# SerialGLCD.net
KiCad netlist of a schematic drawn in EAGLE
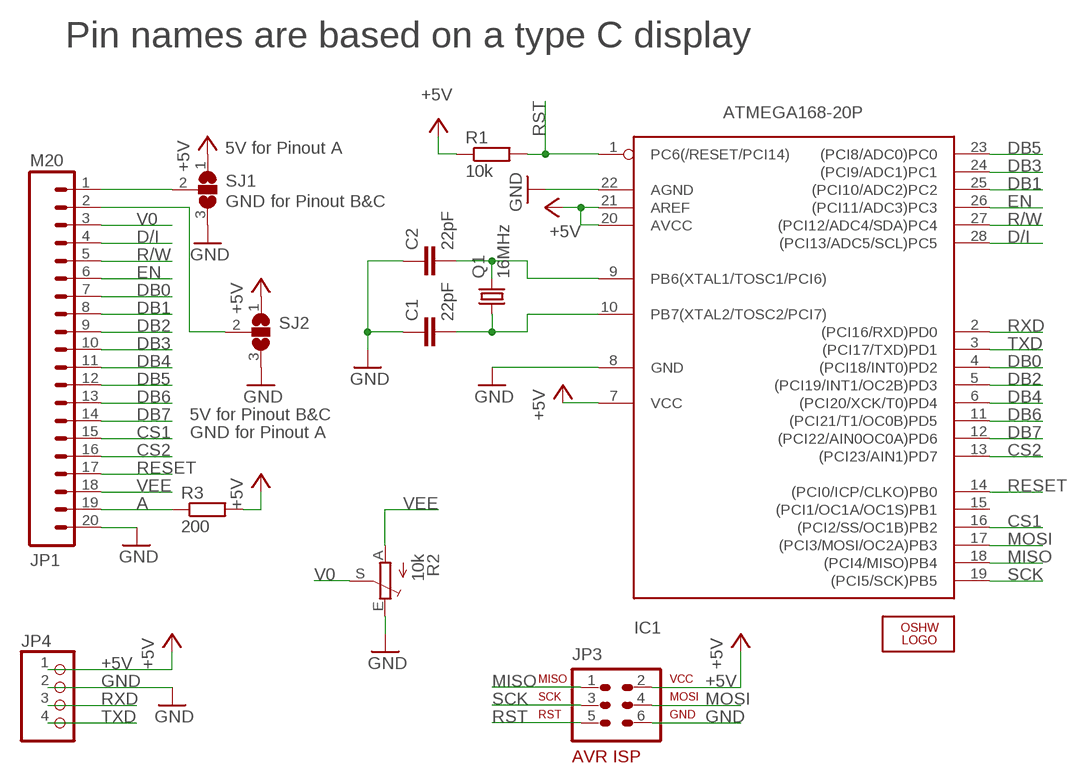
[diagram p0: schematic, sheet 1]

(export (version "E")
  (design (tool "Eeschema 10.0.6"))
  (components
    (comp (ref "C1")
      (value "22pF")
      (footprint "eagle-import:C025-024X044")
      (libsource (lib "eagle-import") (part "C-EU025-024X044"))
    )
    (comp (ref "C2")
      (value "22pF")
      (footprint "eagle-import:C025-024X044")
      (libsource (lib "eagle-import") (part "C-EU025-024X044"))
    )
    (comp (ref "IC1")
      (value "ATMEGA168-20P")
      (footprint "eagle-import:DIL28-3")
      (libsource (lib "eagle-import") (part "ATMEGA168P-20"))
    )
    (comp (ref "JP1")
      (value "M20")
      (footprint "eagle-import:1X20")
      (libsource (lib "eagle-import") (part "M20"))
    )
    (comp (ref "JP3")
      (value "AVR-ISP-6VERT")
      (footprint "eagle-import:AVR-ISP-6")
      (libsource (lib "eagle-import") (part "AVR-ISP-6VERT"))
    )
    (comp (ref "JP4")
      (value "PINHD-1X4/90")
      (footprint "eagle-import:1X04_90")
      (libsource (lib "eagle-import") (part "PINHD-1X4/90"))
    )
    (comp (ref "LOGO1")
      (value "OSHW_LOGO_FILLX0100-NT")
      (footprint "eagle-import:OSHW_FILLX100_NOTEXT")
      (libsource (lib "eagle-import") (part "OSHW_LOGO_FILLX0100-NT"))
    )
    (comp (ref "Q1")
      (value "16MHz")
      (footprint "eagle-import:HC49U-V")
      (libsource (lib "eagle-import") (part "CRYSTALHC49U-V"))
    )
    (comp (ref "R1")
      (value "10k")
      (footprint "eagle-import:0207_10")
      (libsource (lib "eagle-import") (part "R-EU_0207/10"))
    )
    (comp (ref "R2")
      (value "10k")
      (footprint "eagle-import:B25P")
      (libsource (lib "eagle-import") (part "TRIM_EU-B25P"))
    )
    (comp (ref "R3")
      (value "200")
      (footprint "eagle-import:0207_10")
      (libsource (lib "eagle-import") (part "R-EU_0207/10"))
    )
    (comp (ref "SJ1")
      (value "SJ2W")
      (footprint "eagle-import:SJ_2")
      (libsource (lib "eagle-import") (part "SJ2W"))
    )
    (comp (ref "SJ2")
      (value "SJ2W")
      (footprint "eagle-import:SJ_2")
      (libsource (lib "eagle-import") (part "SJ2W"))
    )
  )
  (nets
    (net (code "1") (name "+5V") (class "Default")
      (node (ref "IC1") (pin "20") (pinfunction "AVCC_20") (pintype "bidirectional"))
      (node (ref "IC1") (pin "21") (pinfunction "AREF_21") (pintype "bidirectional"))
      (node (ref "IC1") (pin "7") (pinfunction "VCC_7") (pintype "bidirectional"))
      (node (ref "JP3") (pin "2") (pinfunction "2_2") (pintype "passive"))
      (node (ref "JP4") (pin "1") (pinfunction "1_1") (pintype "passive"))
      (node (ref "R1") (pin "1") (pinfunction "1_1") (pintype "passive"))
      (node (ref "R3") (pin "2") (pinfunction "2_2") (pintype "passive"))
      (node (ref "SJ1") (pin "1") (pinfunction "1_1") (pintype "passive"))
      (node (ref "SJ2") (pin "1") (pinfunction "1_1") (pintype "passive"))
    )
    (net (code "2") (name "/A") (class "Default")
      (node (ref "JP1") (pin "19") (pinfunction "19_19") (pintype "passive"))
      (node (ref "R3") (pin "1") (pinfunction "1_1") (pintype "passive"))
    )
    (net (code "3") (name "/CS1") (class "Default")
      (node (ref "IC1") (pin "16") (pinfunction "(PCI2/SS/OC1B)PB2_16") (pintype "bidirectional"))
      (node (ref "JP1") (pin "15") (pinfunction "15_15") (pintype "passive"))
    )
    (net (code "4") (name "/CS2") (class "Default")
      (node (ref "IC1") (pin "13") (pinfunction "(PCI23/AIN1)PD7_13") (pintype "bidirectional"))
      (node (ref "JP1") (pin "16") (pinfunction "16_16") (pintype "passive"))
    )
    (net (code "5") (name "/DB0") (class "Default")
      (node (ref "IC1") (pin "4") (pinfunction "(PCI18/INT0)PD2_4") (pintype "bidirectional"))
      (node (ref "JP1") (pin "7") (pinfunction "7_7") (pintype "passive"))
    )
    (net (code "6") (name "/DB1") (class "Default")
      (node (ref "IC1") (pin "25") (pinfunction "(PCI10/ADC2)PC2_25") (pintype "bidirectional"))
      (node (ref "JP1") (pin "8") (pinfunction "8_8") (pintype "passive"))
    )
    (net (code "7") (name "/DB2") (class "Default")
      (node (ref "IC1") (pin "5") (pinfunction "(PCI19/INT1/OC2B)PD3_5") (pintype "bidirectional"))
      (node (ref "JP1") (pin "9") (pinfunction "9_9") (pintype "passive"))
    )
    (net (code "8") (name "/DB3") (class "Default")
      (node (ref "IC1") (pin "24") (pinfunction "(PCI9/ADC1)PC1_24") (pintype "bidirectional"))
      (node (ref "JP1") (pin "10") (pinfunction "10_10") (pintype "passive"))
    )
    (net (code "9") (name "/DB4") (class "Default")
      (node (ref "IC1") (pin "6") (pinfunction "(PCI20/XCK/T0)PD4_6") (pintype "bidirectional"))
      (node (ref "JP1") (pin "11") (pinfunction "11_11") (pintype "passive"))
    )
    (net (code "10") (name "/DB5") (class "Default")
      (node (ref "IC1") (pin "23") (pinfunction "(PCI8/ADC0)PC0_23") (pintype "bidirectional"))
      (node (ref "JP1") (pin "12") (pinfunction "12_12") (pintype "passive"))
    )
    (net (code "11") (name "/DB6") (class "Default")
      (node (ref "IC1") (pin "11") (pinfunction "(PCI21/T1/OC0B)PD5_11") (pintype "bidirectional"))
      (node (ref "JP1") (pin "13") (pinfunction "13_13") (pintype "passive"))
    )
    (net (code "12") (name "/DB7") (class "Default")
      (node (ref "IC1") (pin "12") (pinfunction "(PCI22/AIN0OC0A)PD6_12") (pintype "bidirectional"))
      (node (ref "JP1") (pin "14") (pinfunction "14_14") (pintype "passive"))
    )
    (net (code "13") (name "/D{slash}I") (class "Default")
      (node (ref "IC1") (pin "28") (pinfunction "(PCI13/ADC5/SCL)PC5_28") (pintype "bidirectional"))
      (node (ref "JP1") (pin "4") (pinfunction "4_4") (pintype "passive"))
    )
    (net (code "14") (name "/EN") (class "Default")
      (node (ref "IC1") (pin "26") (pinfunction "(PCI11/ADC3)PC3_26") (pintype "bidirectional"))
      (node (ref "JP1") (pin "6") (pinfunction "6_6") (pintype "passive"))
    )
    (net (code "15") (name "/MISO") (class "Default")
      (node (ref "IC1") (pin "18") (pinfunction "(PCI4/MISO)PB4_18") (pintype "bidirectional"))
      (node (ref "JP3") (pin "1") (pinfunction "1_1") (pintype "passive"))
    )
    (net (code "16") (name "/MOSI") (class "Default")
      (node (ref "IC1") (pin "17") (pinfunction "(PCI3/MOSI/OC2A)PB3_17") (pintype "bidirectional"))
      (node (ref "JP3") (pin "4") (pinfunction "4_4") (pintype "passive"))
    )
    (net (code "17") (name "/RESET") (class "Default")
      (node (ref "IC1") (pin "14") (pinfunction "(PCI0/ICP/CLKO)PB0_14") (pintype "bidirectional"))
      (node (ref "JP1") (pin "17") (pinfunction "17_17") (pintype "passive"))
    )
    (net (code "18") (name "/RST") (class "Default")
      (node (ref "IC1") (pin "1") (pinfunction "PC6(/RESET/PCI14)_1") (pintype "bidirectional"))
      (node (ref "JP3") (pin "5") (pinfunction "5_5") (pintype "passive"))
      (node (ref "R1") (pin "2") (pinfunction "2_2") (pintype "passive"))
    )
    (net (code "19") (name "/RXD") (class "Default")
      (node (ref "IC1") (pin "2") (pinfunction "(PCI16/RXD)PD0_2") (pintype "bidirectional"))
      (node (ref "JP4") (pin "3") (pinfunction "3_3") (pintype "passive"))
    )
    (net (code "20") (name "/R{slash}W") (class "Default")
      (node (ref "IC1") (pin "27") (pinfunction "(PCI12/ADC4/SDA)PC4_27") (pintype "bidirectional"))
      (node (ref "JP1") (pin "5") (pinfunction "5_5") (pintype "passive"))
    )
    (net (code "21") (name "/SCK") (class "Default")
      (node (ref "IC1") (pin "19") (pinfunction "(PCI5/SCK)PB5_19") (pintype "bidirectional"))
      (node (ref "JP3") (pin "3") (pinfunction "3_3") (pintype "passive"))
    )
    (net (code "22") (name "/TXD") (class "Default")
      (node (ref "IC1") (pin "3") (pinfunction "(PCI17/TXD)PD1_3") (pintype "bidirectional"))
      (node (ref "JP4") (pin "4") (pinfunction "4_4") (pintype "passive"))
    )
    (net (code "23") (name "/V0") (class "Default")
      (node (ref "JP1") (pin "3") (pinfunction "3_3") (pintype "passive"))
      (node (ref "R2") (pin "S") (pinfunction "S_S") (pintype "passive"))
    )
    (net (code "24") (name "/VEE") (class "Default")
      (node (ref "JP1") (pin "18") (pinfunction "18_18") (pintype "passive"))
      (node (ref "R2") (pin "A") (pinfunction "A_A") (pintype "passive"))
    )
    (net (code "25") (name "GND") (class "Default")
      (node (ref "C1") (pin "1") (pinfunction "1_1") (pintype "passive"))
      (node (ref "C2") (pin "1") (pinfunction "1_1") (pintype "passive"))
      (node (ref "IC1") (pin "22") (pinfunction "AGND_22") (pintype "bidirectional"))
      (node (ref "IC1") (pin "8") (pinfunction "GND_8") (pintype "bidirectional"))
      (node (ref "JP1") (pin "20") (pinfunction "20_20") (pintype "passive"))
      (node (ref "JP3") (pin "6") (pinfunction "6_6") (pintype "passive"))
      (node (ref "JP4") (pin "2") (pinfunction "2_2") (pintype "passive"))
      (node (ref "R2") (pin "E") (pinfunction "E_E") (pintype "passive"))
      (node (ref "SJ1") (pin "3") (pinfunction "3_3") (pintype "passive"))
      (node (ref "SJ2") (pin "3") (pinfunction "3_3") (pintype "passive"))
    )
    (net (code "26") (name "Net-(IC1-PB6(XTAL1{slash}TOSC1{slash}PCI6))") (class "Default")
      (node (ref "C2") (pin "2") (pinfunction "2_2") (pintype "passive"))
      (node (ref "IC1") (pin "9") (pinfunction "PB6(XTAL1/TOSC1/PCI6)_9") (pintype "bidirectional"))
      (node (ref "Q1") (pin "2") (pinfunction "2_2") (pintype "passive"))
    )
    (net (code "27") (name "Net-(IC1-PB7(XTAL2{slash}TOSC2{slash}PCI7))") (class "Default")
      (node (ref "C1") (pin "2") (pinfunction "2_2") (pintype "passive"))
      (node (ref "IC1") (pin "10") (pinfunction "PB7(XTAL2/TOSC2/PCI7)_10") (pintype "bidirectional"))
      (node (ref "Q1") (pin "1") (pinfunction "1_1") (pintype "passive"))
    )
    (net (code "28") (name "Net-(JP1-Pad1)") (class "Default")
      (node (ref "JP1") (pin "1") (pinfunction "1_1") (pintype "passive"))
      (node (ref "SJ1") (pin "2") (pinfunction "2_2") (pintype "passive"))
    )
    (net (code "29") (name "Net-(JP1-Pad2)") (class "Default")
      (node (ref "JP1") (pin "2") (pinfunction "2_2") (pintype "passive"))
      (node (ref "SJ2") (pin "2") (pinfunction "2_2") (pintype "passive"))
    )
    (net (code "30") (name "unconnected-(IC1-(PCI1{slash}OC1A{slash}OC1S)PB1-Pad15)") (class "Default")
      (node (ref "IC1") (pin "15") (pinfunction "(PCI1/OC1A/OC1S)PB1_15") (pintype "bidirectional"))
    )
  )
)
